# RTC_SDCARD.net
KiCad netlist of a schematic drawn in Altium Designer
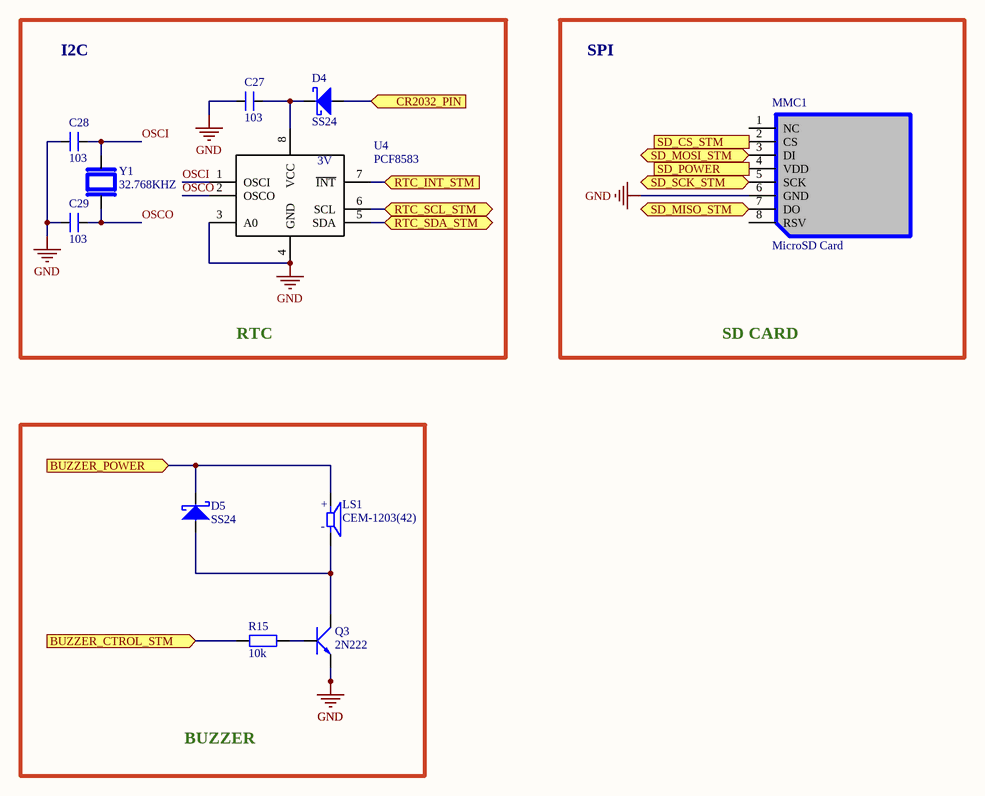
[diagram p0: RTC_SDCARD.SchDoc]

(export (version "E")
  (design (tool "Eeschema 10.0.6"))
  (components
    (comp (ref "C27")
      (value "103")
      (footprint "SM-0805")
      (description "Cap SMD")
      (libsource (lib "KhanhBK_Library_4") (part "CM"))
    )
    (comp (ref "C28")
      (value "103")
      (footprint "SM-0805")
      (description "Cap SMD")
      (libsource (lib "KhanhBK_Library_4") (part "CM"))
    )
    (comp (ref "C29")
      (value "103")
      (footprint "SM-0805")
      (description "Cap SMD")
      (libsource (lib "KhanhBK_Library_4") (part "CM"))
    )
    (comp (ref "D4")
      (value "SS24")
      (footprint "DIO-SMD-106")
      (description "Diode Schottky")
      (fields (field (name "PART NUMBER") "LED 3 ly Single Colour"))
      (libsource (lib "KhanhBK_Library_4") (part "Diode Schottky"))
    )
    (comp (ref "D5")
      (value "SS24")
      (footprint "DIO-SMD-106")
      (description "Diode Schottky")
      (fields (field (name "PART NUMBER") "LED 3 ly Single Colour"))
      (libsource (lib "KhanhBK_Library_4") (part "Diode Schottky"))
    )
    (comp (ref "LS1")
      (value "CEM-1203(42)")
      (footprint "CUI_CEM-1203(42)")
      (description "12 mm, 3.5 V, 85 dB, Through Hole, Magnetic Audio Transducer Buzzer")
      (fields (field (name "MF") "CUI Devices"))
      (libsource (lib "BUZZER_CEM_1203_42") (part "CEM-1203(42)"))
    )
    (comp (ref "MMC1")
      (value "MicroSD Card")
      (footprint "MicroSD-2")
      (libsource (lib "Devzone_SCHLib") (part "MicroSD Card"))
    )
    (comp (ref "Q3")
      (value "2N222")
      (footprint "SOT23-231")
      (description "NPN 600mW, ECB")
      (libsource (lib "KhanhBK_Library_4") (part "2N222"))
    )
    (comp (ref "R15")
      (value "10k")
      (footprint "RES-1/4W")
      (description "Resistor R1/4W")
      (libsource (lib "KhanhBK_Library_4") (part "R"))
    )
    (comp (ref "U4")
      (value "PCF8583")
      (footprint "SO8L")
      (description "I2C REAL TIME CLOCK")
      (fields
        (field (name "MANUFACTURER PART NUMBER") "PCF8583T/5,518")
        (field (name "MANUFACTURER") "NXP Semiconductors")
      )
      (libsource (lib "KhanhBK_SCH_Library_2") (part "PCF8583"))
    )
    (comp (ref "Y1")
      (value "32.768KHZ")
      (footprint "XTAL_AB26T-32.768KHZ-E:XTAL_AB26T-32.768KHZ-E")
      (description "32.768kHz WATCH CRYSTAL, 6.2 x 02.1MM CYLINDER PACKAGE")
      (fields (field (name "MP") "AB26T-32.768KHZ-E") (field (name "MF") "Abracon LLC"))
      (libsource (lib "AB26T-32.768KHZ-E") (part "AB26T-32.768KHZ-E"))
    )
  )
  (nets
    (net (code "1") (name "/BUZZER_CTROL_STM") (class "Default")
      (node (ref "R15") (pin "2") (pinfunction "2_2") (pintype "passive"))
    )
    (net (code "2") (name "/BUZZER_POWER") (class "Default")
      (node (ref "D5") (pin "2") (pinfunction "2_2") (pintype "passive"))
      (node (ref "LS1") (pin "P") (pinfunction "P_P") (pintype "passive"))
    )
    (net (code "3") (name "/CR2032_PIN") (class "Default")
      (node (ref "D4") (pin "1") (pinfunction "1_1") (pintype "passive"))
    )
    (net (code "4") (name "/OSCI") (class "Default")
      (node (ref "C28") (pin "1") (pinfunction "1_1") (pintype "passive"))
      (node (ref "U4") (pin "1") (pinfunction "OSCI_1") (pintype "passive"))
      (node (ref "Y1") (pin "1") (pinfunction "1_1") (pintype "passive"))
    )
    (net (code "5") (name "/OSCO") (class "Default")
      (node (ref "C29") (pin "2") (pinfunction "2_2") (pintype "passive"))
      (node (ref "U4") (pin "2") (pinfunction "OSCO_2") (pintype "passive"))
      (node (ref "Y1") (pin "2") (pinfunction "2_2") (pintype "passive"))
    )
    (net (code "6") (name "/RTC_INT_STM") (class "Default")
      (node (ref "U4") (pin "7") (pinfunction "~{INT}_7") (pintype "passive"))
    )
    (net (code "7") (name "/RTC_SCL_STM") (class "Default")
      (node (ref "U4") (pin "6") (pinfunction "SCL_6") (pintype "passive"))
    )
    (net (code "8") (name "/RTC_SDA_STM") (class "Default")
      (node (ref "U4") (pin "5") (pinfunction "SDA_5") (pintype "passive"))
    )
    (net (code "9") (name "/SD_CS_STM") (class "Default")
      (node (ref "MMC1") (pin "2") (pinfunction "CS_2") (pintype "passive"))
    )
    (net (code "10") (name "/SD_MISO_STM") (class "Default")
      (node (ref "MMC1") (pin "7") (pinfunction "DO_7") (pintype "passive"))
    )
    (net (code "11") (name "/SD_MOSI_STM") (class "Default")
      (node (ref "MMC1") (pin "3") (pinfunction "DI_3") (pintype "passive"))
    )
    (net (code "12") (name "/SD_POWER") (class "Default")
      (node (ref "MMC1") (pin "4") (pinfunction "VDD_4") (pintype "passive"))
    )
    (net (code "13") (name "/SD_SCK_STM") (class "Default")
      (node (ref "MMC1") (pin "5") (pinfunction "SCK_5") (pintype "passive"))
    )
    (net (code "14") (name "GND") (class "Default")
      (node (ref "C27") (pin "2") (pinfunction "2_2") (pintype "passive"))
      (node (ref "C28") (pin "2") (pinfunction "2_2") (pintype "passive"))
      (node (ref "C29") (pin "1") (pinfunction "1_1") (pintype "passive"))
      (node (ref "MMC1") (pin "6") (pinfunction "GND_6") (pintype "passive"))
      (node (ref "Q3") (pin "1") (pinfunction "E_1") (pintype "passive"))
      (node (ref "U4") (pin "3") (pinfunction "A0_3") (pintype "passive"))
      (node (ref "U4") (pin "4") (pinfunction "GND_4") (pintype "passive"))
    )
    (net (code "15") (name "Net-(Q3-B)") (class "Default")
      (node (ref "Q3") (pin "2") (pinfunction "B_2") (pintype "passive"))
      (node (ref "R15") (pin "1") (pinfunction "1_1") (pintype "passive"))
    )
    (net (code "16") (name "Net-(Q3-C)") (class "Default")
      (node (ref "D5") (pin "1") (pinfunction "1_1") (pintype "passive"))
      (node (ref "LS1") (pin "N") (pinfunction "N_N") (pintype "passive"))
      (node (ref "Q3") (pin "3") (pinfunction "C_3") (pintype "passive"))
    )
    (net (code "17") (name "Net-(U4-VCC)") (class "Default")
      (node (ref "C27") (pin "1") (pinfunction "1_1") (pintype "passive"))
      (node (ref "D4") (pin "2") (pinfunction "2_2") (pintype "passive"))
      (node (ref "U4") (pin "8") (pinfunction "VCC_8") (pintype "passive"))
    )
    (net (code "18") (name "unconnected-(MMC1-NC-Pad1)") (class "Default")
      (node (ref "MMC1") (pin "1") (pinfunction "NC_1") (pintype "passive"))
    )
    (net (code "19") (name "unconnected-(MMC1-RSV-Pad8)") (class "Default")
      (node (ref "MMC1") (pin "8") (pinfunction "RSV_8") (pintype "passive"))
    )
  )
)
